# Copy_of_ST_LINK_V2-1.net
KiCad netlist of a schematic drawn in Altium Designer
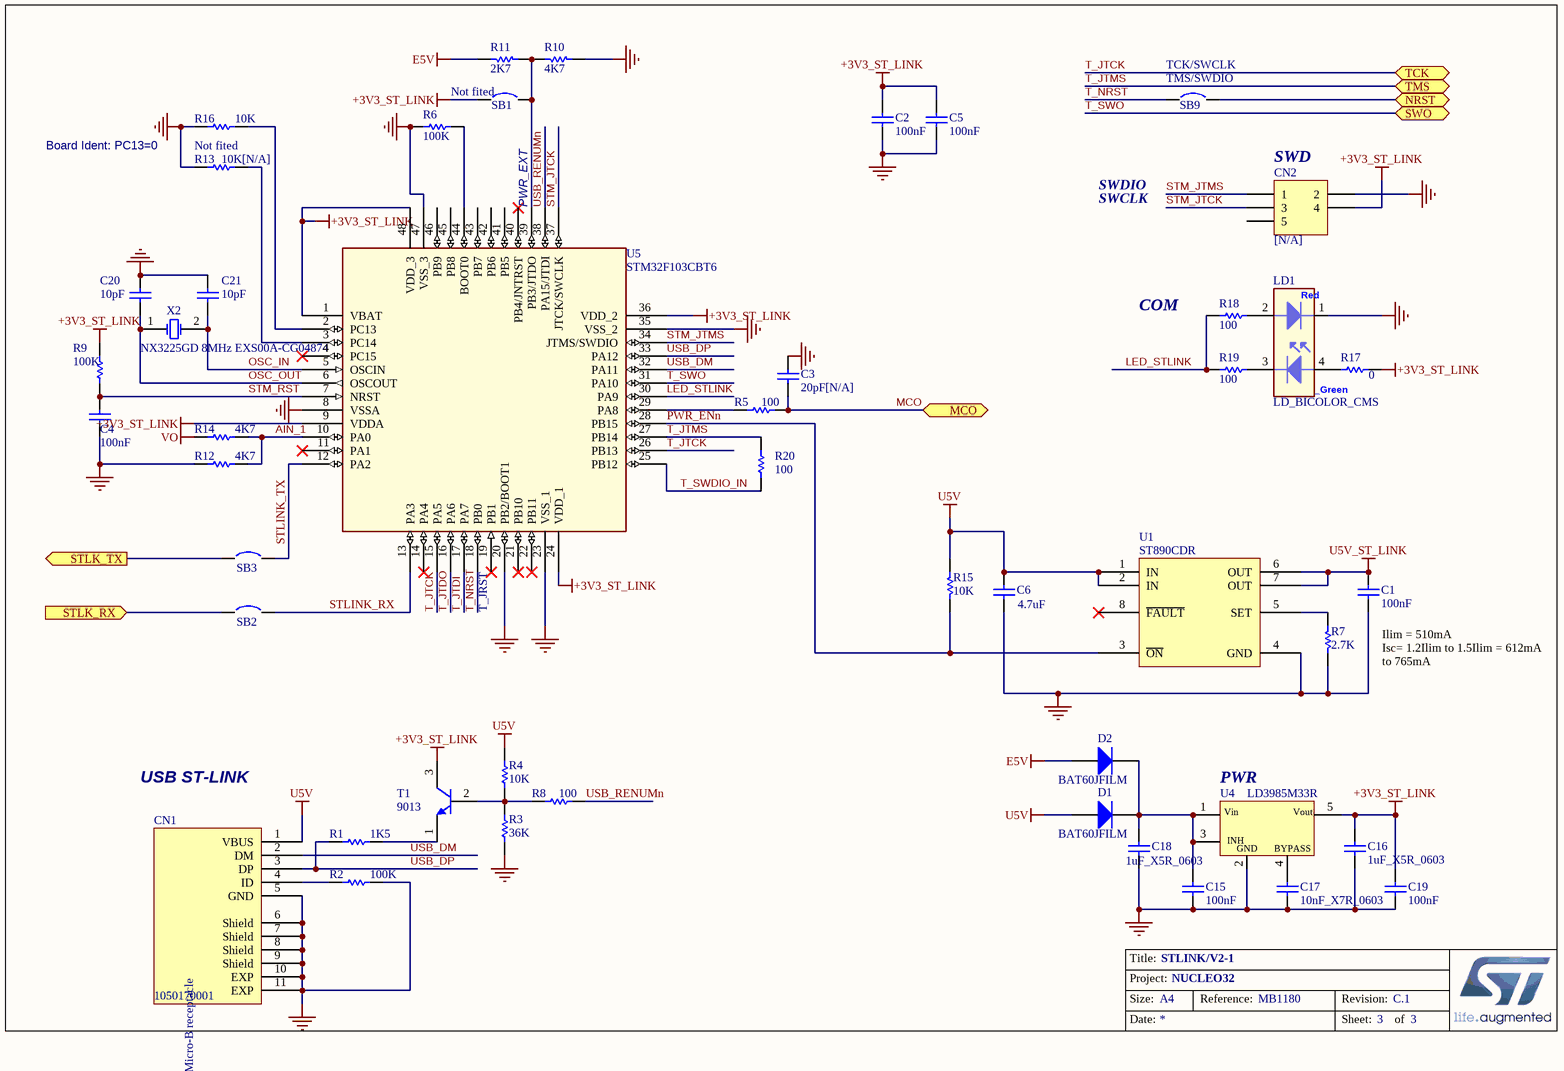
[diagram p0: Copy of ST_LINK_V2-1.SCHDOC]

(export (version "E")
  (design (tool "Eeschema 10.0.6"))
  (components
    (comp (ref "C1")
      (value "100nF")
      (footprint "0603C")
      (description "Capacitor 0402 / 0603 / 0805")
      (libsource (lib "MCD_TOOLS") (part "Capacitor_ST"))
    )
    (comp (ref "C2")
      (value "100nF")
      (footprint "0603C")
      (description "Capacitor 0402 / 0603 / 0805")
      (libsource (lib "MCD_TOOLS") (part "Capacitor_ST"))
    )
    (comp (ref "C3")
      (value "20pF[N/A]")
      (footprint "0603C")
      (description "Capacitor 0402 / 0603 / 0805")
      (libsource (lib "MCD_TOOLS") (part "Capacitor_ST"))
    )
    (comp (ref "C4")
      (value "100nF")
      (footprint "0603C")
      (description "Capacitor 0402 / 0603 / 0805")
      (libsource (lib "MCD_TOOLS") (part "Capacitor_ST"))
    )
    (comp (ref "C5")
      (value "100nF")
      (footprint "0603C")
      (description "Capacitor 0402 / 0603 / 0805")
      (libsource (lib "MCD_TOOLS") (part "Capacitor_ST"))
    )
    (comp (ref "C6")
      (value "4.7uF")
      (footprint "0603C")
      (description "0603  X5R 1µF")
      (fields (field (name "TOLERANCE") "10%"))
      (libsource (lib "MB963_1") (part "CAP SMD 0603  X5R 1µF 25V 10%"))
    )
    (comp (ref "C15")
      (value "100nF")
      (footprint "0603C")
      (description "Capacitor 0402 / 0603 / 0805")
      (libsource (lib "MCD_TOOLS") (part "Capacitor_ST"))
    )
    (comp (ref "C16")
      (value "1uF_X5R_0603")
      (footprint "0603C")
      (description "0603  X5R 1µF")
      (fields (field (name "TOLERANCE") "10%"))
      (libsource (lib "MB963_1") (part "CAP SMD 0603  X5R 1µF 25V 10%"))
    )
    (comp (ref "C17")
      (value "10nF_X7R_0603")
      (footprint "0603C")
      (description "0603  X7R 10NF")
      (fields (field (name "TOLERANCE") "10%"))
      (libsource (lib "MB963_1") (part "CAP SMD 0603  X7R 10000PF 50V 10%"))
    )
    (comp (ref "C18")
      (value "1uF_X5R_0603")
      (footprint "0603C")
      (description "0603  X5R 1µF")
      (fields (field (name "TOLERANCE") "10%"))
      (libsource (lib "MB963_1") (part "CAP SMD 0603  X5R 1µF 25V 10%"))
    )
    (comp (ref "C19")
      (value "100nF")
      (footprint "0603C")
      (description "Capacitor 0402 / 0603 / 0805")
      (libsource (lib "MCD_TOOLS") (part "Capacitor_ST"))
    )
    (comp (ref "C20")
      (value "10pF")
      (footprint "0603C")
      (description "Capacitor 0402 / 0603 / 0805")
      (libsource (lib "MCD_TOOLS") (part "Capacitor_ST"))
    )
    (comp (ref "C21")
      (value "10pF")
      (footprint "0603C")
      (description "Capacitor 0402 / 0603 / 0805")
      (libsource (lib "MCD_TOOLS") (part "Capacitor_ST"))
    )
    (comp (ref "CN1")
      (value "1050170001")
      (footprint "Molex_1050170001")
      (libsource (lib "Smartphone_accessory") (part "1050170001"))
    )
    (comp (ref "CN2")
      (value "[N/A]")
      (footprint "HDR_1x5_2R54_V_M")
      (description "Header, 3-Pin, Dual row")
      (fields (field (name "PUBLISHER") "Altium Limited"))
      (libsource (lib "Miscellaneous Connectors") (part "Header 3X2"))
    )
    (comp (ref "D1")
      (value "BAT60JFILM")
      (footprint "SOD-323")
      (libsource (lib "MCD_TOOLS") (part "BAT60JFILM"))
    )
    (comp (ref "D2")
      (value "BAT60JFILM")
      (footprint "SOD-323")
      (libsource (lib "MCD_TOOLS") (part "BAT60JFILM"))
    )
    (comp (ref "LD1")
      (value "LD_BICOLOR_CMS")
      (footprint "HSMF-A201")
      (description "Bicolor Led")
      (libsource (lib "MCD_TOOLS") (part "LD_BICOLOR_CMS"))
    )
    (comp (ref "R1")
      (value "1K5")
      (footprint "0603R")
      (description "Resistor 0402 / 0603 / 0805")
      (libsource (lib "Miscellaneous Devices") (part "Res1"))
    )
    (comp (ref "R2")
      (value "100K")
      (footprint "0603R")
      (description "Resistor 0402 / 0603 / 0805")
      (libsource (lib "Miscellaneous Devices") (part "Res1"))
    )
    (comp (ref "R3")
      (value "36K")
      (footprint "0603R")
      (description "Resistor")
      (fields (field (name "PUBLISHER") "Altium Limited"))
      (libsource (lib "") (part "Res1_1"))
    )
    (comp (ref "R4")
      (value "10K")
      (footprint "0603R")
      (description "Resistor")
      (fields (field (name "PUBLISHER") "Altium Limited"))
      (libsource (lib "") (part "Res1_1"))
    )
    (comp (ref "R5")
      (value "100")
      (footprint "0603R")
      (description "Resistor 0402 / 0603 / 0805")
      (libsource (lib "Miscellaneous Devices") (part "Res1"))
    )
    (comp (ref "R6")
      (value "100K")
      (footprint "0603R")
      (description "Resistor 0402 / 0603 / 0805")
      (libsource (lib "Miscellaneous Devices") (part "Res1"))
    )
    (comp (ref "R7")
      (value "2.7K")
      (footprint "0603R")
      (description "Resistor")
      (fields (field (name "PUBLISHER") "Altium Limited"))
      (libsource (lib "*") (part "Res1"))
    )
    (comp (ref "R8")
      (value "100")
      (footprint "0603R")
      (description "Resistor 0402 / 0603 / 0805")
      (libsource (lib "Miscellaneous Devices") (part "Res1"))
    )
    (comp (ref "R9")
      (value "100K")
      (footprint "0603R")
      (description "Resistor 0402 / 0603 / 0805")
      (libsource (lib "Miscellaneous Devices") (part "Res1"))
    )
    (comp (ref "R10")
      (value "4K7")
      (footprint "0603R")
      (description "Resistor")
      (fields (field (name "PUBLISHER") "Altium Limited"))
      (libsource (lib "") (part "Res1_2"))
    )
    (comp (ref "R11")
      (value "2K7")
      (footprint "0603R")
      (description "Resistor")
      (fields (field (name "PUBLISHER") "Altium Limited"))
      (libsource (lib "") (part "Res1_2"))
    )
    (comp (ref "R12")
      (value "4K7")
      (footprint "0603R")
      (description "Resistor 0402 / 0603 / 0805")
      (libsource (lib "Miscellaneous Devices") (part "Res1"))
    )
    (comp (ref "R13")
      (value "10K[N/A]")
      (footprint "0603R")
      (description "Resistor 0402 / 0603 / 0805")
      (libsource (lib "Miscellaneous Devices") (part "Res1"))
    )
    (comp (ref "R14")
      (value "4K7")
      (footprint "0603R")
      (description "Resistor 0402 / 0603 / 0805")
      (libsource (lib "Miscellaneous Devices") (part "Res1"))
    )
    (comp (ref "R15")
      (value "10K")
      (footprint "0603R")
      (description "Resistor")
      (fields (field (name "PUBLISHER") "Altium Limited"))
      (libsource (lib "*") (part "Res1"))
    )
    (comp (ref "R16")
      (value "10K")
      (footprint "0603R")
      (description "Resistor 0402 / 0603 / 0805")
      (libsource (lib "Miscellaneous Devices") (part "Res1"))
    )
    (comp (ref "R17")
      (value "0")
      (footprint "0603R")
      (description "Resistor 0402 / 0603 / 0805")
      (libsource (lib "Miscellaneous Devices") (part "Res1"))
    )
    (comp (ref "R18")
      (value "100")
      (footprint "0603R")
      (description "Resistor 0402 / 0603 / 0805")
      (libsource (lib "Miscellaneous Devices") (part "Res1"))
    )
    (comp (ref "R19")
      (value "100")
      (footprint "0603R")
      (description "Resistor 0402 / 0603 / 0805")
      (libsource (lib "Miscellaneous Devices") (part "Res1"))
    )
    (comp (ref "R20")
      (value "100")
      (footprint "0603R")
      (description "Resistor 0402 / 0603 / 0805")
      (libsource (lib "Miscellaneous Devices") (part "Res1"))
    )
    (comp (ref "SB1")
      (value "Circuit Breaker (open)")
      (footprint "SB_0603")
      (description "Circuit Breaker")
      (fields (field (name "PUBLISHER") "Altium Limited"))
      (libsource (lib "MB915") (part "Circuit Breaker"))
    )
    (comp (ref "SB2")
      (value "Circuit Breaker (close)")
      (footprint "SB_0603")
      (description "Circuit Breaker")
      (fields (field (name "PUBLISHER") "Altium Limited"))
      (libsource (lib "MCD_TOOLS") (part "Circuit Breaker"))
    )
    (comp (ref "SB3")
      (value "Circuit Breaker (close)")
      (footprint "SB_0603")
      (description "Circuit Breaker")
      (fields (field (name "PUBLISHER") "Altium Limited"))
      (libsource (lib "MCD_TOOLS") (part "Circuit Breaker"))
    )
    (comp (ref "SB9")
      (value "Circuit Breaker (close)")
      (footprint "SB_0603")
      (description "Circuit Breaker")
      (fields (field (name "PUBLISHER") "Altium Limited"))
      (libsource (lib "MB915") (part "Circuit Breaker"))
    )
    (comp (ref "T1")
      (value "9013")
      (footprint "SOT23-3")
      (description "NPN Bipolar Transistor")
      (fields (field (name "PUBLISHER") "Altium Limited"))
      (libsource (lib "Miscellaneous Devices") (part "NPN"))
    )
    (comp (ref "U1") (value "ST890CDR") (footprint "SO-8") (libsource (lib "MB1180") (part "ST890CDR")))
    (comp (ref "U4")
      (value "LD3985M33R")
      (footprint "SOT23-5L")
      (description "Ultra low drop-low noise BiCMOS voltage, regulators low ESR capacitors compatible")
      (libsource (lib "MCD_TOOLS") (part "LD3985M33R"))
    )
    (comp (ref "U5")
      (value "STM32F103CBT6")
      (footprint "LQFP48_0R5_7x7")
      (description "Medium-density performance line ARM-based 32-bit MCU with 64KB Flash")
      (libsource (lib "Nucleo_64") (part "STM32F103CBT6"))
    )
    (comp (ref "X2")
      (value "NX3225GD 8MHz EXS00A-CG04874")
      (footprint "XTAL_2SM_3R2x2R5")
      (description "Crystal Oscillator")
      (fields (field (name "PUBLISHER") "Altium Limited"))
      (libsource (lib "MB963_1") (part "XTAL"))
    )
  )
  (nets
    (net (code "1") (name "+3V3_ST_LINK") (class "Default")
      (node (ref "C16") (pin "1") (pinfunction "1_1") (pintype "passive"))
      (node (ref "C19") (pin "2") (pinfunction "2_2") (pintype "passive"))
      (node (ref "C2") (pin "2") (pinfunction "2_2") (pintype "passive"))
      (node (ref "C5") (pin "2") (pinfunction "2_2") (pintype "passive"))
      (node (ref "CN2") (pin "4") (pinfunction "4_4") (pintype "passive"))
      (node (ref "R17") (pin "2") (pinfunction "2_2") (pintype "passive"))
      (node (ref "R9") (pin "2") (pinfunction "2_2") (pintype "passive"))
      (node (ref "SB1") (pin "1") (pinfunction "1_1") (pintype "passive"))
      (node (ref "T1") (pin "3") (pinfunction "C_3") (pintype "passive"))
      (node (ref "U4") (pin "5") (pinfunction "Vout_5") (pintype "passive"))
      (node (ref "U5") (pin "1") (pinfunction "VBAT_1") (pintype "power_in"))
      (node (ref "U5") (pin "24") (pinfunction "VDD_1_24") (pintype "power_in"))
      (node (ref "U5") (pin "36") (pinfunction "VDD_2_36") (pintype "power_in"))
      (node (ref "U5") (pin "48") (pinfunction "VDD_3_48") (pintype "power_in"))
      (node (ref "U5") (pin "9") (pinfunction "VDDA_9") (pintype "power_in"))
    )
    (net (code "2") (name "/AIN_1") (class "Default")
      (node (ref "R12") (pin "2") (pinfunction "2_2") (pintype "passive"))
      (node (ref "R14") (pin "2") (pinfunction "2_2") (pintype "passive"))
      (node (ref "U5") (pin "10") (pinfunction "PA0_10") (pintype "bidirectional"))
    )
    (net (code "3") (name "/LED_STLINK") (class "Default")
      (node (ref "R18") (pin "1") (pinfunction "1_1") (pintype "passive"))
      (node (ref "R19") (pin "1") (pinfunction "1_1") (pintype "passive"))
      (node (ref "U5") (pin "30") (pinfunction "PA9_30") (pintype "bidirectional"))
    )
    (net (code "4") (name "/MCO") (class "Default")
      (node (ref "C3") (pin "1") (pinfunction "1_1") (pintype "passive"))
      (node (ref "R5") (pin "2") (pinfunction "2_2") (pintype "passive"))
    )
    (net (code "5") (name "/NRST") (class "Default")
      (node (ref "SB9") (pin "2") (pinfunction "2_2") (pintype "passive"))
    )
    (net (code "6") (name "/OSC_IN") (class "Default")
      (node (ref "C21") (pin "1") (pinfunction "1_1") (pintype "passive"))
      (node (ref "U5") (pin "5") (pinfunction "OSCIN_5") (pintype "input"))
      (node (ref "X2") (pin "2") (pinfunction "OSC2_2") (pintype "passive"))
    )
    (net (code "7") (name "/OSC_OUT") (class "Default")
      (node (ref "C20") (pin "1") (pinfunction "1_1") (pintype "passive"))
      (node (ref "U5") (pin "6") (pinfunction "OSCOUT_6") (pintype "output"))
      (node (ref "X2") (pin "1") (pinfunction "OSC1_1") (pintype "passive"))
    )
    (net (code "8") (name "/PWR_ENn") (class "Default")
      (node (ref "R15") (pin "2") (pinfunction "2_2") (pintype "passive"))
      (node (ref "U1") (pin "3") (pinfunction "~{ON}_3") (pintype "passive"))
      (node (ref "U5") (pin "28") (pinfunction "PB15_28") (pintype "bidirectional"))
    )
    (net (code "9") (name "/STLINK_RX") (class "Default")
      (node (ref "SB2") (pin "2") (pinfunction "2_2") (pintype "passive"))
      (node (ref "U5") (pin "13") (pinfunction "PA3_13") (pintype "bidirectional"))
    )
    (net (code "10") (name "/STLINK_TX") (class "Default")
      (node (ref "SB3") (pin "2") (pinfunction "2_2") (pintype "passive"))
      (node (ref "U5") (pin "12") (pinfunction "PA2_12") (pintype "bidirectional"))
    )
    (net (code "11") (name "/STLK_RX") (class "Default")
      (node (ref "SB2") (pin "1") (pinfunction "1_1") (pintype "passive"))
    )
    (net (code "12") (name "/STLK_TX") (class "Default")
      (node (ref "SB3") (pin "1") (pinfunction "1_1") (pintype "passive"))
    )
    (net (code "13") (name "/STM_JTCK") (class "Default")
      (node (ref "CN2") (pin "3") (pinfunction "3_3") (pintype "passive"))
      (node (ref "U5") (pin "37") (pinfunction "JTCK/SWCLK_37") (pintype "bidirectional"))
    )
    (net (code "14") (name "/STM_JTMS") (class "Default")
      (node (ref "CN2") (pin "1") (pinfunction "1_1") (pintype "passive"))
      (node (ref "U5") (pin "34") (pinfunction "JTMS/SWDIO_34") (pintype "bidirectional"))
    )
    (net (code "15") (name "/STM_RST") (class "Default")
      (node (ref "C4") (pin "2") (pinfunction "2_2") (pintype "passive"))
      (node (ref "R9") (pin "1") (pinfunction "1_1") (pintype "passive"))
      (node (ref "U5") (pin "7") (pinfunction "NRST_7") (pintype "input"))
    )
    (net (code "16") (name "/T_JTCK") (class "Default")
      (node (ref "U5") (pin "15") (pinfunction "PA5_15") (pintype "bidirectional"))
      (node (ref "U5") (pin "26") (pinfunction "PB13_26") (pintype "bidirectional"))
    )
    (net (code "17") (name "/T_JTDI") (class "Default")
      (node (ref "U5") (pin "17") (pinfunction "PA7_17") (pintype "bidirectional"))
    )
    (net (code "18") (name "/T_JTDO") (class "Default")
      (node (ref "U5") (pin "16") (pinfunction "PA6_16") (pintype "bidirectional"))
    )
    (net (code "19") (name "/T_JTMS") (class "Default")
      (node (ref "R20") (pin "2") (pinfunction "2_2") (pintype "passive"))
      (node (ref "U5") (pin "27") (pinfunction "PB14_27") (pintype "bidirectional"))
    )
    (net (code "20") (name "/T_NRST") (class "Default")
      (node (ref "SB9") (pin "1") (pinfunction "1_1") (pintype "passive"))
      (node (ref "U5") (pin "18") (pinfunction "PB0_18") (pintype "bidirectional"))
    )
    (net (code "21") (name "/T_SWDIO_IN") (class "Default")
      (node (ref "R20") (pin "1") (pinfunction "1_1") (pintype "passive"))
      (node (ref "U5") (pin "25") (pinfunction "PB12_25") (pintype "bidirectional"))
    )
    (net (code "22") (name "/T_SWO") (class "Default")
      (node (ref "U5") (pin "31") (pinfunction "PA10_31") (pintype "bidirectional"))
    )
    (net (code "23") (name "/USB_DM") (class "Default")
      (node (ref "CN1") (pin "2") (pinfunction "DM_2") (pintype "passive"))
      (node (ref "U5") (pin "32") (pinfunction "PA11_32") (pintype "bidirectional"))
    )
    (net (code "24") (name "/USB_DP") (class "Default")
      (node (ref "CN1") (pin "3") (pinfunction "DP_3") (pintype "passive"))
      (node (ref "R1") (pin "1") (pinfunction "1_1") (pintype "passive"))
      (node (ref "U5") (pin "33") (pinfunction "PA12_33") (pintype "bidirectional"))
    )
    (net (code "25") (name "/USB_RENUMn") (class "Default")
      (node (ref "R8") (pin "2") (pinfunction "2_2") (pintype "passive"))
      (node (ref "U5") (pin "38") (pinfunction "PA15/JTDI_38") (pintype "bidirectional"))
    )
    (net (code "26") (name "E5V") (class "Default")
      (node (ref "D2") (pin "1") (pinfunction "A_1") (pintype "passive"))
      (node (ref "R11") (pin "1") (pinfunction "1_1") (pintype "passive"))
    )
    (net (code "27") (name "GND") (class "Default")
      (node (ref "C1") (pin "1") (pinfunction "1_1") (pintype "passive"))
      (node (ref "C15") (pin "1") (pinfunction "1_1") (pintype "passive"))
      (node (ref "C16") (pin "2") (pinfunction "2_2") (pintype "passive"))
      (node (ref "C17") (pin "1") (pinfunction "1_1") (pintype "passive"))
      (node (ref "C18") (pin "1") (pinfunction "1_1") (pintype "passive"))
      (node (ref "C19") (pin "1") (pinfunction "1_1") (pintype "passive"))
      (node (ref "C2") (pin "1") (pinfunction "1_1") (pintype "passive"))
      (node (ref "C20") (pin "2") (pinfunction "2_2") (pintype "passive"))
      (node (ref "C21") (pin "2") (pinfunction "2_2") (pintype "passive"))
      (node (ref "C3") (pin "2") (pinfunction "2_2") (pintype "passive"))
      (node (ref "C4") (pin "1") (pinfunction "1_1") (pintype "passive"))
      (node (ref "C5") (pin "1") (pinfunction "1_1") (pintype "passive"))
      (node (ref "C6") (pin "1") (pinfunction "1_1") (pintype "passive"))
      (node (ref "CN1") (pin "10") (pinfunction "EXP_10") (pintype "passive"))
      (node (ref "CN1") (pin "11") (pinfunction "EXP_11") (pintype "passive"))
      (node (ref "CN1") (pin "5") (pinfunction "GND_5") (pintype "passive"))
      (node (ref "CN1") (pin "6") (pinfunction "Shield_6") (pintype "passive"))
      (node (ref "CN1") (pin "7") (pinfunction "Shield_7") (pintype "passive"))
      (node (ref "CN1") (pin "8") (pinfunction "Shield_8") (pintype "passive"))
      (node (ref "CN1") (pin "9") (pinfunction "Shield_9") (pintype "passive"))
      (node (ref "CN2") (pin "2") (pinfunction "2_2") (pintype "passive"))
      (node (ref "LD1") (pin "1") (pinfunction "1_1") (pintype "passive"))
      (node (ref "R10") (pin "2") (pinfunction "2_2") (pintype "passive"))
      (node (ref "R12") (pin "1") (pinfunction "1_1") (pintype "passive"))
      (node (ref "R13") (pin "1") (pinfunction "1_1") (pintype "passive"))
      (node (ref "R16") (pin "1") (pinfunction "1_1") (pintype "passive"))
      (node (ref "R2") (pin "2") (pinfunction "2_2") (pintype "passive"))
      (node (ref "R3") (pin "1") (pinfunction "1_1") (pintype "passive"))
      (node (ref "R6") (pin "1") (pinfunction "1_1") (pintype "passive"))
      (node (ref "R7") (pin "2") (pinfunction "2_2") (pintype "passive"))
      (node (ref "U1") (pin "4") (pinfunction "GND_4") (pintype "passive"))
      (node (ref "U4") (pin "2") (pinfunction "GND_2") (pintype "passive"))
      (node (ref "U5") (pin "20") (pinfunction "PB2/BOOT1_20") (pintype "bidirectional"))
      (node (ref "U5") (pin "23") (pinfunction "VSS_1_23") (pintype "power_in"))
      (node (ref "U5") (pin "35") (pinfunction "VSS_2_35") (pintype "power_in"))
      (node (ref "U5") (pin "47") (pinfunction "VSS_3_47") (pintype "power_in"))
      (node (ref "U5") (pin "8") (pinfunction "VSSA_8") (pintype "power_in"))
    )
    (net (code "28") (name "Net-(CN1-ID)") (class "Default")
      (node (ref "CN1") (pin "4") (pinfunction "ID_4") (pintype "passive"))
      (node (ref "R2") (pin "1") (pinfunction "1_1") (pintype "passive"))
    )
    (net (code "29") (name "Net-(D1-K)") (class "Default")
      (node (ref "C15") (pin "2") (pinfunction "2_2") (pintype "passive"))
      (node (ref "C18") (pin "2") (pinfunction "2_2") (pintype "passive"))
      (node (ref "D1") (pin "2") (pinfunction "K_2") (pintype "passive"))
      (node (ref "D2") (pin "2") (pinfunction "K_2") (pintype "passive"))
      (node (ref "U4") (pin "1") (pinfunction "Vin_1") (pintype "passive"))
      (node (ref "U4") (pin "3") (pinfunction "CE_3") (pintype "passive"))
    )
    (net (code "30") (name "Net-(LD1-Pad2)") (class "Default")
      (node (ref "LD1") (pin "2") (pinfunction "2_2") (pintype "passive"))
      (node (ref "R18") (pin "2") (pinfunction "2_2") (pintype "passive"))
    )
    (net (code "31") (name "Net-(LD1-Pad3)") (class "Default")
      (node (ref "LD1") (pin "3") (pinfunction "3_3") (pintype "passive"))
      (node (ref "R19") (pin "2") (pinfunction "2_2") (pintype "passive"))
    )
    (net (code "32") (name "Net-(LD1-Pad4)") (class "Default")
      (node (ref "LD1") (pin "4") (pinfunction "4_4") (pintype "passive"))
      (node (ref "R17") (pin "1") (pinfunction "1_1") (pintype "passive"))
    )
    (net (code "33") (name "Net-(T1-B)") (class "Default")
      (node (ref "R3") (pin "2") (pinfunction "2_2") (pintype "passive"))
      (node (ref "R4") (pin "1") (pinfunction "1_1") (pintype "passive"))
      (node (ref "R8") (pin "1") (pinfunction "1_1") (pintype "passive"))
      (node (ref "T1") (pin "2") (pinfunction "B_2") (pintype "passive"))
    )
    (net (code "34") (name "Net-(T1-E)") (class "Default")
      (node (ref "R1") (pin "2") (pinfunction "2_2") (pintype "passive"))
      (node (ref "T1") (pin "1") (pinfunction "E_1") (pintype "passive"))
    )
    (net (code "35") (name "Net-(U1-SET)") (class "Default")
      (node (ref "R7") (pin "1") (pinfunction "1_1") (pintype "passive"))
      (node (ref "U1") (pin "5") (pinfunction "SET_5") (pintype "passive"))
    )
    (net (code "36") (name "Net-(U4-BYPASS)") (class "Default")
      (node (ref "C17") (pin "2") (pinfunction "2_2") (pintype "passive"))
      (node (ref "U4") (pin "4") (pinfunction "BYPASS_4") (pintype "passive"))
    )
    (net (code "37") (name "Net-(U5-BOOT0)") (class "Default")
      (node (ref "R6") (pin "2") (pinfunction "2_2") (pintype "passive"))
      (node (ref "U5") (pin "44") (pinfunction "BOOT0_44") (pintype "bidirectional"))
    )
    (net (code "38") (name "Net-(U5-PA8)") (class "Default")
      (node (ref "R5") (pin "1") (pinfunction "1_1") (pintype "passive"))
      (node (ref "U5") (pin "29") (pinfunction "PA8_29") (pintype "bidirectional"))
    )
    (net (code "39") (name "Net-(U5-PB3{slash}JTDO)") (class "Default")
      (node (ref "R10") (pin "1") (pinfunction "1_1") (pintype "passive"))
      (node (ref "R11") (pin "2") (pinfunction "2_2") (pintype "passive"))
      (node (ref "SB1") (pin "2") (pinfunction "2_2") (pintype "passive"))
      (node (ref "U5") (pin "39") (pinfunction "PB3/JTDO_39") (pintype "bidirectional"))
    )
    (net (code "40") (name "Net-(U5-PC13)") (class "Default")
      (node (ref "R16") (pin "2") (pinfunction "2_2") (pintype "passive"))
      (node (ref "U5") (pin "2") (pinfunction "PC13_2") (pintype "bidirectional"))
    )
    (net (code "41") (name "Net-(U5-PC14)") (class "Default")
      (node (ref "R13") (pin "2") (pinfunction "2_2") (pintype "passive"))
      (node (ref "U5") (pin "3") (pinfunction "PC14_3") (pintype "bidirectional"))
    )
    (net (code "42") (name "U5V") (class "Default")
      (node (ref "C6") (pin "2") (pinfunction "2_2") (pintype "passive"))
      (node (ref "CN1") (pin "1") (pinfunction "VBUS_1") (pintype "passive"))
      (node (ref "D1") (pin "1") (pinfunction "A_1") (pintype "passive"))
      (node (ref "R15") (pin "1") (pinfunction "1_1") (pintype "passive"))
      (node (ref "R4") (pin "2") (pinfunction "2_2") (pintype "passive"))
      (node (ref "U1") (pin "1") (pinfunction "IN_1") (pintype "passive"))
      (node (ref "U1") (pin "2") (pinfunction "IN_2") (pintype "passive"))
    )
    (net (code "43") (name "U5V_ST_LINK") (class "Default")
      (node (ref "C1") (pin "2") (pinfunction "2_2") (pintype "passive"))
      (node (ref "U1") (pin "6") (pinfunction "OUT_6") (pintype "passive"))
      (node (ref "U1") (pin "7") (pinfunction "OUT_7") (pintype "passive"))
    )
    (net (code "44") (name "VO") (class "Default")
      (node (ref "R14") (pin "1") (pinfunction "1_1") (pintype "passive"))
    )
    (net (code "45") (name "unconnected-(CN2-Pad5)") (class "Default")
      (node (ref "CN2") (pin "5") (pinfunction "5_5") (pintype "passive"))
    )
    (net (code "46") (name "unconnected-(U1-~{FAULT}-Pad8)") (class "Default")
      (node (ref "U1") (pin "8") (pinfunction "~{FAULT}_8") (pintype "passive+no_connect"))
    )
    (net (code "47") (name "unconnected-(U5-PA1-Pad11)") (class "Default")
      (node (ref "U5") (pin "11") (pinfunction "PA1_11") (pintype "bidirectional+no_connect"))
    )
    (net (code "48") (name "unconnected-(U5-PA4-Pad14)") (class "Default")
      (node (ref "U5") (pin "14") (pinfunction "PA4_14") (pintype "bidirectional+no_connect"))
    )
    (net (code "49") (name "unconnected-(U5-PB1-Pad19)") (class "Default")
      (node (ref "U5") (pin "19") (pinfunction "PB1_19") (pintype "input+no_connect"))
    )
    (net (code "50") (name "unconnected-(U5-PB4{slash}JNTRST-Pad40)") (class "Default")
      (node (ref "U5") (pin "40") (pinfunction "PB4/JNTRST_40") (pintype "bidirectional+no_connect"))
    )
    (net (code "51") (name "unconnected-(U5-PB5-Pad41)") (class "Default")
      (node (ref "U5") (pin "41") (pinfunction "PB5_41") (pintype "bidirectional"))
    )
    (net (code "52") (name "unconnected-(U5-PB6-Pad42)") (class "Default")
      (node (ref "U5") (pin "42") (pinfunction "PB6_42") (pintype "bidirectional"))
    )
    (net (code "53") (name "unconnected-(U5-PB7-Pad43)") (class "Default")
      (node (ref "U5") (pin "43") (pinfunction "PB7_43") (pintype "bidirectional"))
    )
    (net (code "54") (name "unconnected-(U5-PB8-Pad45)") (class "Default")
      (node (ref "U5") (pin "45") (pinfunction "PB8_45") (pintype "bidirectional"))
    )
    (net (code "55") (name "unconnected-(U5-PB9-Pad46)") (class "Default")
      (node (ref "U5") (pin "46") (pinfunction "PB9_46") (pintype "bidirectional"))
    )
    (net (code "56") (name "unconnected-(U5-PB10-Pad21)") (class "Default")
      (node (ref "U5") (pin "21") (pinfunction "PB10_21") (pintype "bidirectional+no_connect"))
    )
    (net (code "57") (name "unconnected-(U5-PB11-Pad22)") (class "Default")
      (node (ref "U5") (pin "22") (pinfunction "PB11_22") (pintype "bidirectional+no_connect"))
    )
    (net (code "58") (name "unconnected-(U5-PC15-Pad4)") (class "Default")
      (node (ref "U5") (pin "4") (pinfunction "PC15_4") (pintype "bidirectional+no_connect"))
    )
  )
)
